# thelast.net
KiCad netlist of a schematic drawn in Altium Designer
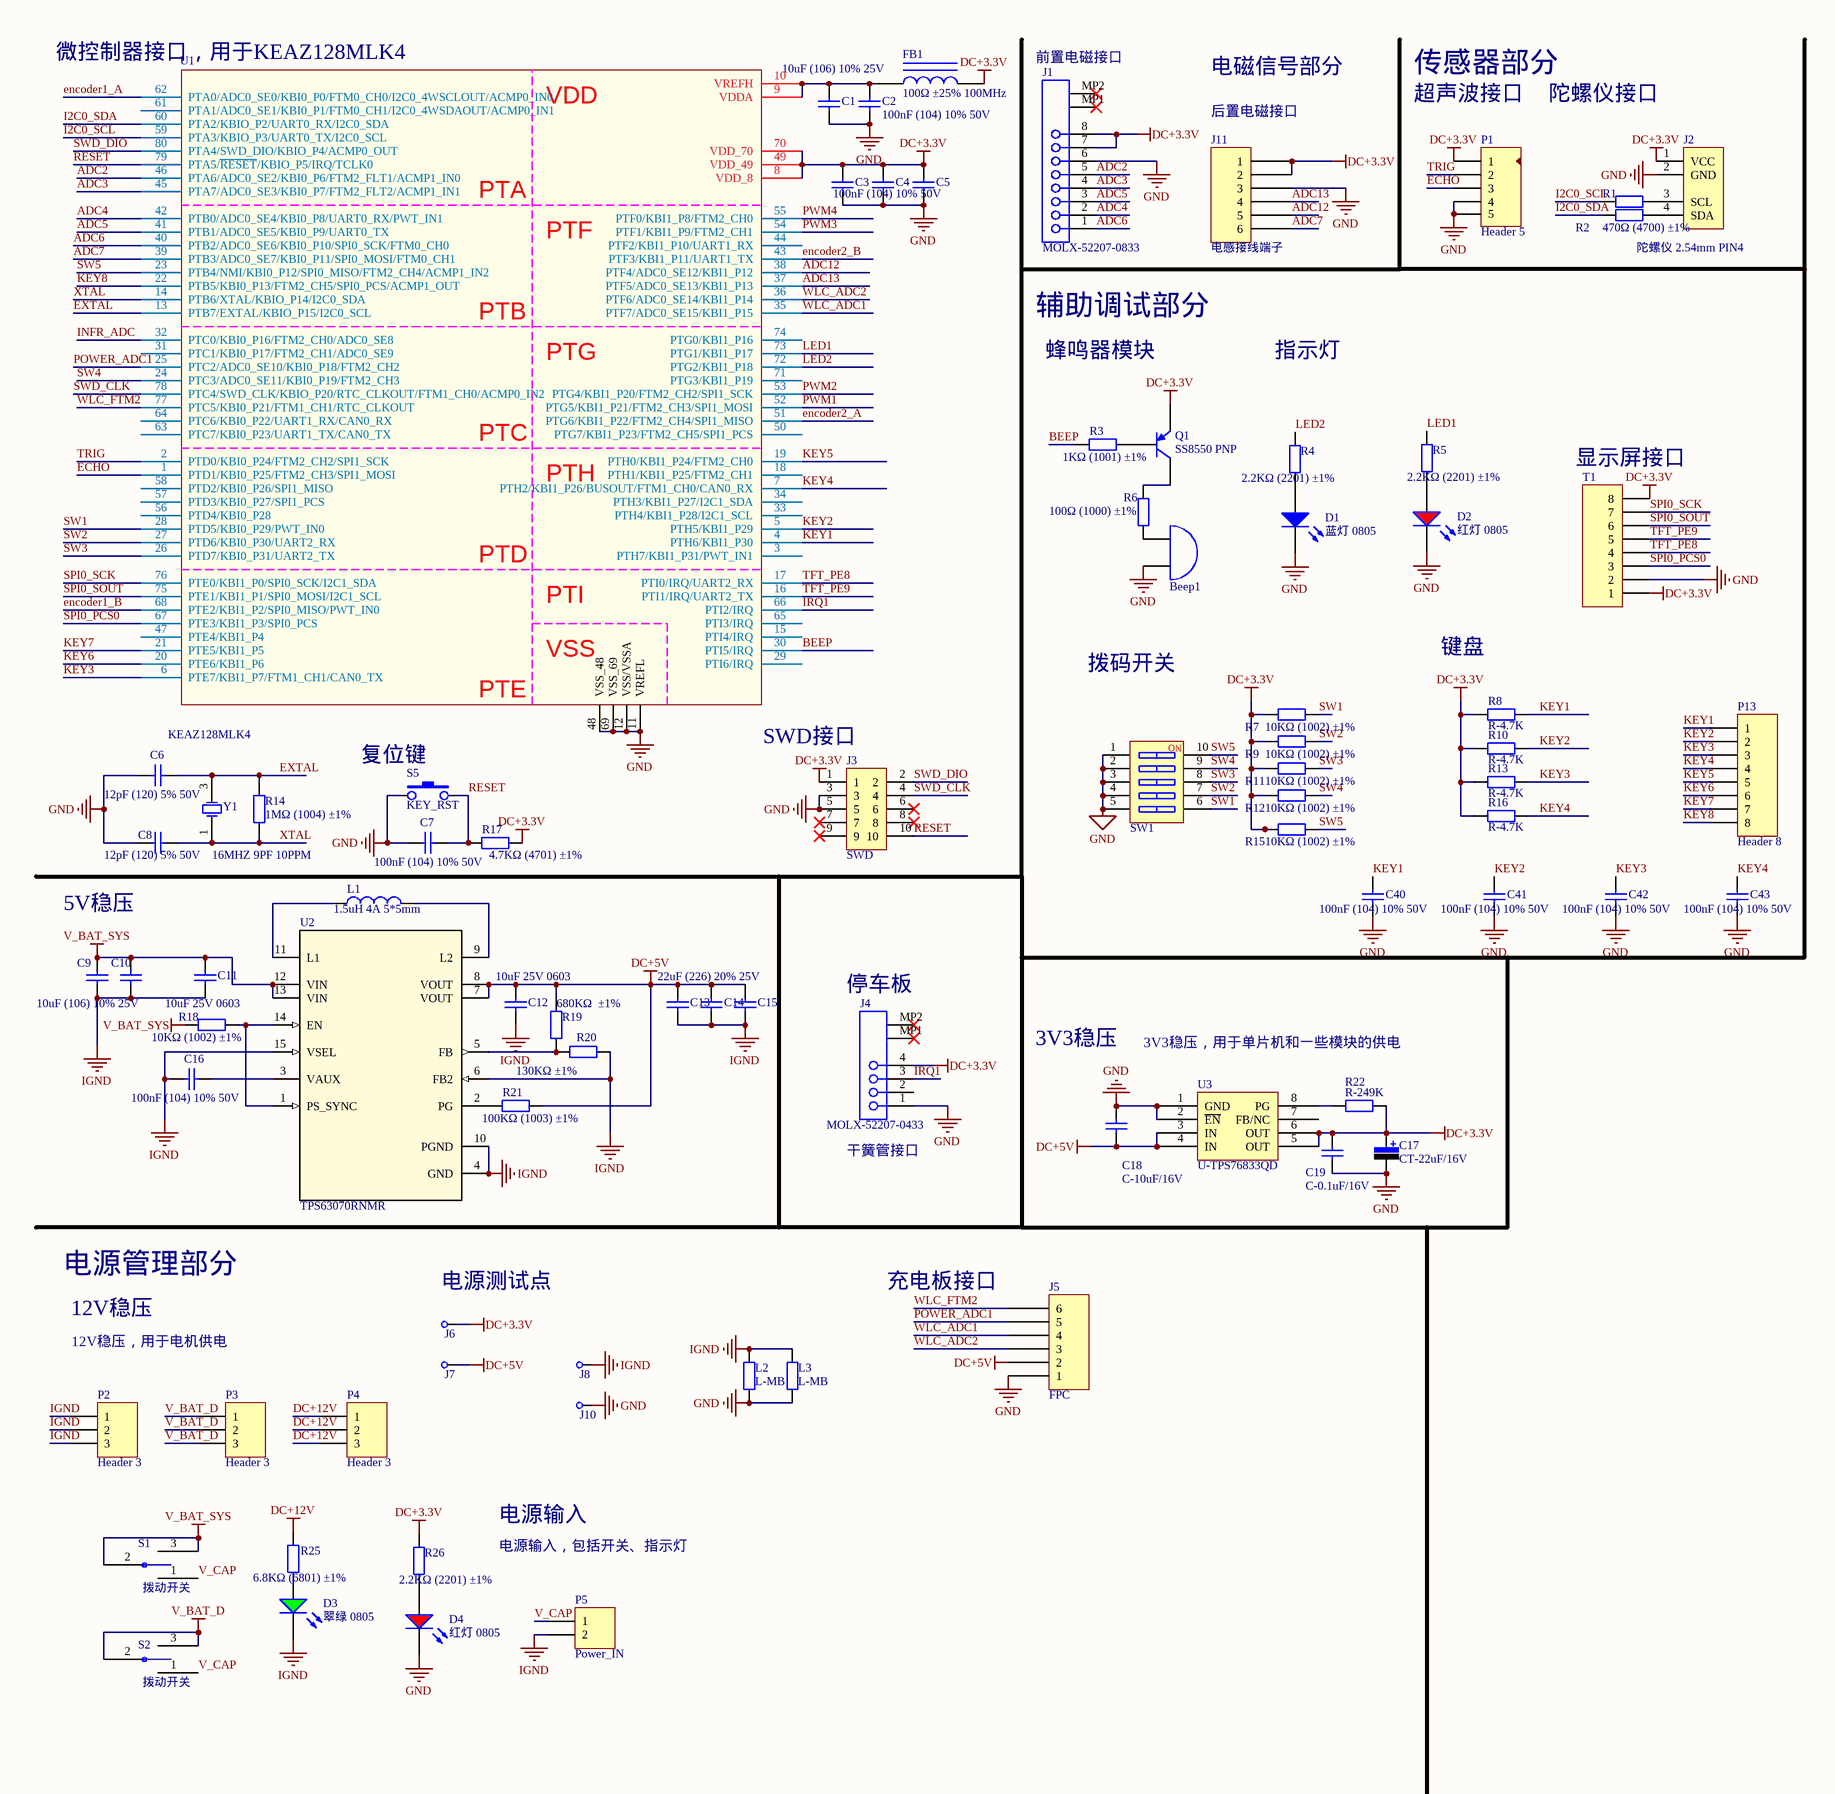
[diagram p0: thelast.SchDoc, left]
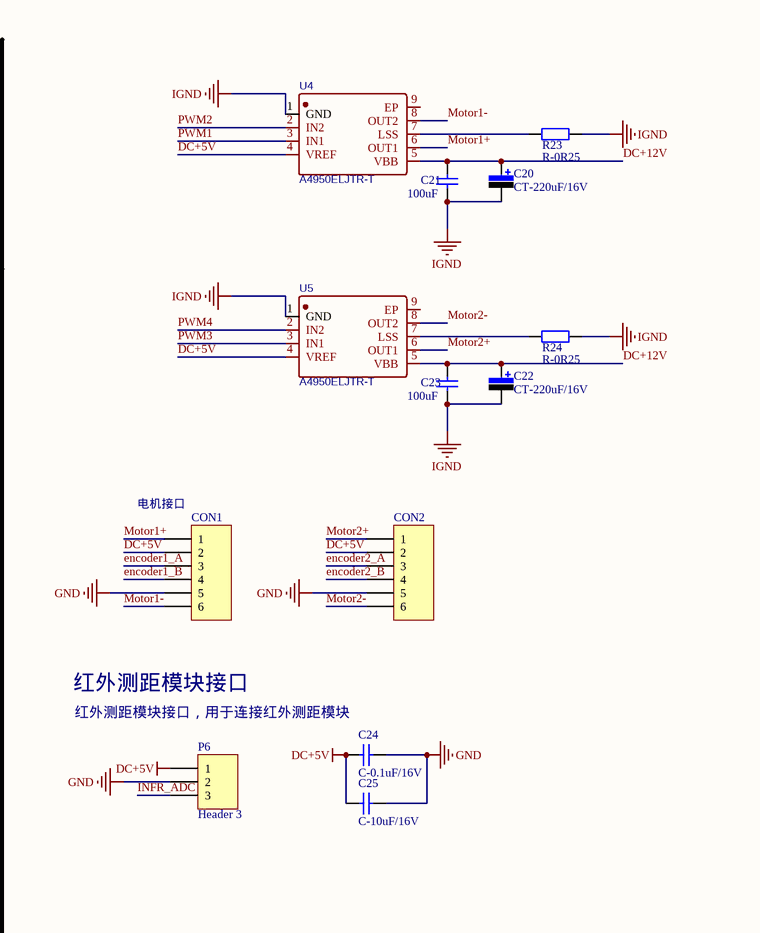
[diagram p1: thelast.SchDoc, right]

(export (version "E")
  (design (tool "Eeschema 10.0.6"))
  (components
    (comp (ref "Beep1") (value "蜂鸣器") (footprint "beep") (libsource (lib "2018NXP") (part "蜂鸣器")))
    (comp (ref "C1")
      (value "10uF (106) 10% 25V")
      (footprint "0603_C")
      (description "贴片电容")
      (libsource (lib "Miscellaneous Devices LC") (part "0805 10uF (106) 10% 25V"))
    )
    (comp (ref "C2")
      (value "100nF (104) 10% 50V")
      (footprint "0603_C")
      (description "贴片电容")
      (libsource (lib "Miscellaneous Devices LC") (part "0603 100nF (104) 10% 50V"))
    )
    (comp (ref "C3")
      (value "100nF (104) 10% 50V")
      (footprint "0603-1")
      (description "贴片电容")
      (libsource (lib "Miscellaneous Devices LC") (part "0603 100nF (104) 10% 50V"))
    )
    (comp (ref "C4")
      (value "100nF (104) 10% 50V")
      (footprint "0603-1")
      (description "贴片电容")
      (libsource (lib "Miscellaneous Devices LC") (part "0603 100nF (104) 10% 50V"))
    )
    (comp (ref "C5")
      (value "100nF (104) 10% 50V")
      (footprint "0603-1")
      (description "贴片电容")
      (libsource (lib "Miscellaneous Devices LC") (part "0603 100nF (104) 10% 50V"))
    )
    (comp (ref "C6")
      (value "12pF (120) 5% 50V")
      (footprint "0603-1")
      (description "贴片电容")
      (libsource (lib "Miscellaneous Devices LC") (part "0603 12pF (120) 5% 50V"))
    )
    (comp (ref "C7")
      (value "100nF (104) 10% 50V")
      (footprint "0603-1")
      (description "贴片电容")
      (libsource (lib "Miscellaneous Devices LC") (part "0603 100nF (104) 10% 50V"))
    )
    (comp (ref "C8")
      (value "12pF (120) 5% 50V")
      (footprint "0603-1")
      (description "贴片电容")
      (libsource (lib "Miscellaneous Devices LC") (part "0603 12pF (120) 5% 50V"))
    )
    (comp (ref "C9")
      (value "10uF (106) 10% 25V")
      (footprint "0805_C")
      (description "贴片电容")
      (libsource (lib "Miscellaneous Devices LC") (part "0805 10uF (106) 10% 25V"))
    )
    (comp (ref "C10")
      (value "10uF (106) 10% 25V")
      (footprint "0805_C")
      (description "贴片电容")
      (libsource (lib "Miscellaneous Devices LC") (part "0805 10uF (106) 10% 25V"))
    )
    (comp (ref "C11")
      (value "10uF 25V 0603")
      (footprint "0603_C")
      (description "贴片电容")
      (libsource (lib "Miscellaneous Devices LC") (part "0603 10uF (106) 10% 10V"))
    )
    (comp (ref "C12")
      (value "10uF 25V 0603")
      (footprint "0603_C")
      (description "贴片电容")
      (libsource (lib "Miscellaneous Devices LC") (part "0603 10uF (106) 10% 10V"))
    )
    (comp (ref "C13")
      (value "22uF (226) 20% 25V")
      (footprint "0805_C")
      (description "贴片电容")
      (libsource (lib "Miscellaneous Devices LC") (part "0805 22uF (226) 20% 25V"))
    )
    (comp (ref "C14")
      (value "22uF (226) 20% 25V")
      (footprint "0805_C")
      (description "贴片电容")
      (libsource (lib "Miscellaneous Devices LC") (part "0805 22uF (226) 20% 25V"))
    )
    (comp (ref "C15")
      (value "22uF (226) 20% 25V")
      (footprint "0805_C")
      (description "贴片电容")
      (libsource (lib "Miscellaneous Devices LC") (part "0805 22uF (226) 20% 25V"))
    )
    (comp (ref "C16")
      (value "100nF (104) 10% 50V")
      (footprint "0603_C")
      (description "贴片电容")
      (libsource (lib "Miscellaneous Devices LC") (part "0603 100nF (104) 10% 50V"))
    )
    (comp (ref "C17")
      (value "CT-22uF/16V")
      (footprint "CAP-3528")
      (description "钽电容")
      (fields (field (name "PUBLISHER") "Altium Limited"))
      (libsource (lib "fszhang") (part "Cap-Pol-A"))
    )
    (comp (ref "C18")
      (value "C-10uF/16V")
      (footprint "0603-1")
      (description "Capacitor")
      (fields (field (name "PUBLISHER") "Altium Limited"))
      (libsource (lib "Miscellaneous Devices") (part "Cap"))
    )
    (comp (ref "C19")
      (value "C-0.1uF/16V")
      (footprint "0603-1")
      (description "Capacitor")
      (fields (field (name "PUBLISHER") "Altium Limited"))
      (libsource (lib "Miscellaneous Devices") (part "Cap"))
    )
    (comp (ref "C20")
      (value "CT-220uF/16V")
      (footprint "CASE-E_7343")
      (description "钽电容")
      (fields (field (name "PUBLISHER") "Altium Limited"))
      (libsource (lib "fszhang") (part "Cap-Pol-A"))
    )
    (comp (ref "C21")
      (value "100uF")
      (footprint "0603-1")
      (description "Capacitor")
      (fields (field (name "PUBLISHER") "Altium Limited"))
      (libsource (lib "Miscellaneous Devices") (part "Cap"))
    )
    (comp (ref "C22")
      (value "CT-220uF/16V")
      (footprint "CASE-E_7343")
      (description "钽电容")
      (fields (field (name "PUBLISHER") "Altium Limited"))
      (libsource (lib "fszhang") (part "Cap-Pol-A"))
    )
    (comp (ref "C23")
      (value "100uF")
      (footprint "0603-1")
      (description "Capacitor")
      (fields (field (name "PUBLISHER") "Altium Limited"))
      (libsource (lib "Miscellaneous Devices") (part "Cap"))
    )
    (comp (ref "C24")
      (value "C-0.1uF/16V")
      (footprint "0603-1")
      (description "Capacitor")
      (fields (field (name "PUBLISHER") "Altium Limited"))
      (libsource (lib "Miscellaneous Devices") (part "Cap"))
    )
    (comp (ref "C25")
      (value "C-10uF/16V")
      (footprint "0603-1")
      (description "Capacitor")
      (fields (field (name "PUBLISHER") "Altium Limited"))
      (libsource (lib "Miscellaneous Devices") (part "Cap"))
    )
    (comp (ref "C40")
      (value "100nF (104) 10% 50V")
      (footprint "0603-1")
      (description "贴片电容")
      (libsource (lib "Miscellaneous Devices LC") (part "0603 100nF (104) 10% 50V"))
    )
    (comp (ref "C41")
      (value "100nF (104) 10% 50V")
      (footprint "0603-1")
      (description "贴片电容")
      (libsource (lib "Miscellaneous Devices LC") (part "0603 100nF (104) 10% 50V"))
    )
    (comp (ref "C42")
      (value "100nF (104) 10% 50V")
      (footprint "0603-1")
      (description "贴片电容")
      (libsource (lib "Miscellaneous Devices LC") (part "0603 100nF (104) 10% 50V"))
    )
    (comp (ref "C43")
      (value "100nF (104) 10% 50V")
      (footprint "0603-1")
      (description "贴片电容")
      (libsource (lib "Miscellaneous Devices LC") (part "0603 100nF (104) 10% 50V"))
    )
    (comp (ref "CON1")
      (value "Header 6")
      (footprint "HDR1X6")
      (description "Header, 6-Pin")
      (fields (field (name "PUBLISHER") "Altium Limited"))
      (libsource (lib "Connectors") (part "Header 6"))
    )
    (comp (ref "CON2")
      (value "Header 6")
      (footprint "HDR1X6")
      (description "Header, 6-Pin")
      (fields (field (name "PUBLISHER") "Altium Limited"))
      (libsource (lib "Connectors") (part "Header 6"))
    )
    (comp (ref "D1")
      (value "蓝灯 0805")
      (footprint "0603_R")
      (description "发光二极管")
      (libsource (lib "Miscellaneous Devices LC") (part "0805 蓝灯"))
    )
    (comp (ref "D2")
      (value "红灯 0805")
      (footprint "0603_R")
      (description "发光二极管")
      (libsource (lib "Miscellaneous Devices LC") (part "0805 红灯"))
    )
    (comp (ref "D3")
      (value "翠绿 0805")
      (footprint "0603_R")
      (description "发光二极管")
      (libsource (lib "Miscellaneous Devices LC") (part "0805 翠绿"))
    )
    (comp (ref "D4")
      (value "红灯 0805")
      (footprint "0603_R")
      (description "发光二极管")
      (libsource (lib "Miscellaneous Devices LC") (part "0805 红灯"))
    )
    (comp (ref "FB1")
      (value "100Ω ±25% 100MHz")
      (footprint "0805-1")
      (description "贴片磁珠")
      (libsource (lib "Miscellaneous Devices LC") (part "0805 100Ω 25% 100MHz"))
    )
    (comp (ref "J1")
      (value "MOLX-52207-0833")
      (footprint "FPC-SMD_8PIN-PITCH1.00-BR_LW10251-08")
      (fields (field (name "MANUFACTURER") "Molex") (field (name "PARTNUMBER") "52207-0833"))
      (libsource (lib "2018NXP") (part "MOLX-52207-0833"))
    )
    (comp (ref "J2")
      (value "陀螺仪 2.54mm PIN4")
      (footprint "2.54排针1X4")
      (libsource (lib "2018NXP") (part "陀螺仪 2.54mm PIN4"))
    )
    (comp (ref "J3") (value "SWD") (footprint "2.54排针2X5") (libsource (lib "2018NXP") (part "SWD PIN-10")))
    (comp (ref "J4")
      (value "MOLX-52207-0433")
      (footprint "MOLX-52207-0433")
      (fields (field (name "MANUFACTURER") "Molex") (field (name "PARTNUMBER") "52207-0433"))
      (libsource (lib "2018NXP") (part "MOLX-52207-0433"))
    )
    (comp (ref "J5") (value "FPC") (footprint "FPC6P") (libsource (lib "") (part "FFC6_1")))
    (comp (ref "J6")
      (value "CHECK")
      (footprint "CHECK-A")
      (description "测试点")
      (libsource (lib "fszhang") (part "CHECK"))
    )
    (comp (ref "J7")
      (value "CHECK")
      (footprint "CHECK-A")
      (description "测试点")
      (libsource (lib "fszhang") (part "CHECK"))
    )
    (comp (ref "J8")
      (value "CHECK")
      (footprint "CHECK-A")
      (description "测试点")
      (libsource (lib "fszhang") (part "CHECK"))
    )
    (comp (ref "J10")
      (value "CHECK")
      (footprint "CHECK-A")
      (description "测试点")
      (libsource (lib "fszhang") (part "CHECK"))
    )
    (comp (ref "J11") (value "电感接线端子") (footprint "FPC6P") (libsource (lib "直立电磁原理图库") (part "FFC6")))
    (comp (ref "L1")
      (value "1.5uH 4A 5*5mm")
      (footprint "Inductor_1.5uH")
      (libsource (lib "2018NXP") (part "贴片电感"))
    )
    (comp (ref "L2")
      (value "L-MB")
      (footprint "0603-1")
      (description "Resistor")
      (fields (field (name "PUBLISHER") "Altium Limited"))
      (libsource (lib "2014-SmartCar-DianCi(V4.0)") (part "Res2"))
    )
    (comp (ref "L3")
      (value "L-MB")
      (footprint "0603-1")
      (description "Resistor")
      (fields (field (name "PUBLISHER") "Altium Limited"))
      (libsource (lib "2014-SmartCar-DianCi(V4.0)") (part "Res2"))
    )
    (comp (ref "P1")
      (value "Header 5")
      (footprint "HDR5X1-2.54")
      (description "接插件")
      (fields (field (name "PUBLISHER") "Altium Limited"))
      (libsource (lib "HDR_fszhang") (part "Header 5"))
    )
    (comp (ref "P2")
      (value "Header 3")
      (footprint "HDR1X3")
      (description "Header, 3-Pin")
      (fields (field (name "PUBLISHER") "Altium Limited"))
      (libsource (lib "Miscellaneous Connectors") (part "Header 3"))
    )
    (comp (ref "P3")
      (value "Header 3")
      (footprint "HDR1X3")
      (description "Header, 3-Pin")
      (fields (field (name "PUBLISHER") "Altium Limited"))
      (libsource (lib "Miscellaneous Connectors") (part "Header 3"))
    )
    (comp (ref "P4")
      (value "Header 3")
      (footprint "HDR1X3")
      (description "Header, 3-Pin")
      (fields (field (name "PUBLISHER") "Altium Limited"))
      (libsource (lib "Miscellaneous Connectors") (part "Header 3"))
    )
    (comp (ref "P5")
      (value "Power_IN")
      (footprint "电源接口")
      (description "Header, 2-Pin")
      (fields (field (name "PUBLISHER") "Altium Limited"))
      (libsource (lib "Miscellaneous Connectors") (part "Header 2"))
    )
    (comp (ref "P6")
      (value "Header 3")
      (footprint "HDR1X3")
      (description "Header, 3-Pin")
      (fields (field (name "PUBLISHER") "Altium Limited"))
      (libsource (lib "Miscellaneous Connectors") (part "Header 3"))
    )
    (comp (ref "P13")
      (value "Header 8")
      (footprint "HDR1X8")
      (description "Header, 8-Pin")
      (fields (field (name "PUBLISHER") "Altium Limited"))
      (libsource (lib "Miscellaneous Connectors") (part "Header 8"))
    )
    (comp (ref "Q1") (value "SS8550 PNP") (footprint "SOT-23Q") (libsource (lib "2018NXP") (part "PNP_1")))
    (comp (ref "R1")
      (value "470Ω (4700) ±1%")
      (footprint "0603_R")
      (description "贴片电阻")
      (libsource (lib "Miscellaneous Devices LC") (part "0603 470Ω (4700) 1%"))
    )
    (comp (ref "R2")
      (value "470Ω (4700) ±1%")
      (footprint "0603_R")
      (description "贴片电阻")
      (libsource (lib "Miscellaneous Devices LC") (part "0603 470Ω (4700) 1%"))
    )
    (comp (ref "R3")
      (value "1KΩ (1001) ±1%")
      (footprint "0603_R")
      (description "贴片电阻")
      (libsource (lib "Miscellaneous Devices LC") (part "0603 1KΩ (1001) 1%"))
    )
    (comp (ref "R4")
      (value "2.2KΩ (2201) ±1%")
      (footprint "0603_R")
      (description "贴片电阻")
      (libsource (lib "Miscellaneous Devices LC") (part "0603 3.3KΩ (3301) 1%"))
    )
    (comp (ref "R5")
      (value "2.2KΩ (2201) ±1%")
      (footprint "0603_R")
      (description "贴片电阻")
      (libsource (lib "Miscellaneous Devices LC") (part "0603 2.2KΩ (2201) 1%"))
    )
    (comp (ref "R6")
      (value "100Ω (1000) ±1%")
      (footprint "0603_R")
      (description "贴片电阻")
      (libsource (lib "Miscellaneous Devices LC") (part "0603 100Ω (1000) 1%"))
    )
    (comp (ref "R7")
      (value "10KΩ (1002) ±1%")
      (footprint "0603_R")
      (description "贴片电阻")
      (libsource (lib "Miscellaneous Devices LC") (part "0603 10KΩ (1002) 1%"))
    )
    (comp (ref "R8")
      (value "R-4.7K")
      (footprint "0603-1")
      (description "Resistor")
      (fields (field (name "PUBLISHER") "Altium Limited"))
      (libsource (lib "Miscellaneous Devices") (part "Res2"))
    )
    (comp (ref "R9")
      (value "10KΩ (1002) ±1%")
      (footprint "0603_R")
      (description "贴片电阻")
      (libsource (lib "Miscellaneous Devices LC") (part "0603 10KΩ (1002) 1%"))
    )
    (comp (ref "R10")
      (value "R-4.7K")
      (footprint "0603-1")
      (description "Resistor")
      (fields (field (name "PUBLISHER") "Altium Limited"))
      (libsource (lib "Miscellaneous Devices") (part "Res2"))
    )
    (comp (ref "R11")
      (value "10KΩ (1002) ±1%")
      (footprint "0603_R")
      (description "贴片电阻")
      (libsource (lib "Miscellaneous Devices LC") (part "0603 10KΩ (1002) 1%"))
    )
    (comp (ref "R12")
      (value "10KΩ (1002) ±1%")
      (footprint "0603_R")
      (description "贴片电阻")
      (libsource (lib "Miscellaneous Devices LC") (part "0603 10KΩ (1002) 1%"))
    )
    (comp (ref "R13")
      (value "R-4.7K")
      (footprint "0603-1")
      (description "Resistor")
      (fields (field (name "PUBLISHER") "Altium Limited"))
      (libsource (lib "Miscellaneous Devices") (part "Res2"))
    )
    (comp (ref "R14")
      (value "1MΩ (1004) ±1%")
      (footprint "0603_R")
      (description "贴片电阻")
      (libsource (lib "Miscellaneous Devices LC") (part "0603 1MΩ (1004) 1%"))
    )
    (comp (ref "R15")
      (value "10KΩ (1002) ±1%")
      (footprint "0603_R")
      (description "贴片电阻")
      (libsource (lib "Miscellaneous Devices LC") (part "0603 10KΩ (1002) 1%"))
    )
    (comp (ref "R16")
      (value "R-4.7K")
      (footprint "0603-1")
      (description "Resistor")
      (fields (field (name "PUBLISHER") "Altium Limited"))
      (libsource (lib "Miscellaneous Devices") (part "Res2"))
    )
    (comp (ref "R17")
      (value "4.7KΩ (4701) ±1%")
      (footprint "0603_R")
      (description "贴片电阻")
      (libsource (lib "Miscellaneous Devices LC") (part "0603 4.7KΩ (4701) 1%"))
    )
    (comp (ref "R18")
      (value "10KΩ (1002) ±1%")
      (footprint "0603_R")
      (description "贴片电阻")
      (libsource (lib "") (part "0603 10KΩ (1002) 1%_1"))
    )
    (comp (ref "R19")
      (value "680KΩ  ±1%")
      (footprint "0603_R")
      (description "贴片电阻")
      (libsource (lib "Miscellaneous Devices LC") (part "0603 330KΩ (3303) 1%"))
    )
    (comp (ref "R20")
      (value "130KΩ ±1%")
      (footprint "0603_R")
      (description "贴片电阻")
      (libsource (lib "Miscellaneous Devices LC") (part "0603 51KΩ (5102) 1%"))
    )
    (comp (ref "R21")
      (value "100KΩ (1003) ±1%")
      (footprint "0603_R")
      (description "贴片电阻")
      (libsource (lib "Miscellaneous Devices LC") (part "0603 100KΩ (1003) 1%"))
    )
    (comp (ref "R22")
      (value "R-249K")
      (footprint "0603-1")
      (description "贴片电阻")
      (fields (field (name "PUBLISHER") "Altium Limited"))
      (libsource (lib "") (part "Res1_1"))
    )
    (comp (ref "R23")
      (value "R-0R25")
      (footprint "2512")
      (description "贴片电阻")
      (fields (field (name "PUBLISHER") "Altium Limited"))
      (libsource (lib "fszhang") (part "Res1"))
    )
    (comp (ref "R24")
      (value "R-0R25")
      (footprint "2512")
      (description "贴片电阻")
      (fields (field (name "PUBLISHER") "Altium Limited"))
      (libsource (lib "fszhang") (part "Res1"))
    )
    (comp (ref "R25")
      (value "6.8KΩ (6801) ±1%")
      (footprint "0603_R")
      (description "贴片电阻")
      (libsource (lib "Miscellaneous Devices LC") (part "0603 3.3KΩ (3301) 1%"))
    )
    (comp (ref "R26")
      (value "2.2KΩ (2201) ±1%")
      (footprint "0603_R")
      (description "贴片电阻")
      (libsource (lib "Miscellaneous Devices LC") (part "0603 2.2KΩ (2201) 1%"))
    )
    (comp (ref "S1") (value "拨动开关") (footprint "SW-TO3") (libsource (lib "2018NXP") (part "拨动开关")))
    (comp (ref "S2") (value "拨动开关") (footprint "SW-TO3") (libsource (lib "2018NXP") (part "拨动开关")))
    (comp (ref "S5")
      (value "KEY_RST")
      (footprint "KEY-K2")
      (description "SMT Tactile ‎Switch")
      (libsource (lib "2018NXP") (part "SMT_SW"))
    )
    (comp (ref "SW1") (value "5P") (footprint "拨码开关DIP-5P") (libsource (lib "2018NXP") (part "拨码开关5P")))
    (comp (ref "T1")
      (value "Header 8")
      (footprint "HDR1X8")
      (description "Header, 8-Pin")
      (fields (field (name "PUBLISHER") "Altium Limited"))
      (libsource (lib "Connectors") (part "Header 8"))
    )
    (comp (ref "U1")
      (value "KEAZ128MLK4")
      (footprint "LQFP80(KEA)")
      (libsource (lib "2018NXP") (part "KEAZ128MLK4"))
    )
    (comp (ref "U2")
      (value "TPS63070RNMR")
      (footprint "RNM0015A")
      (description "Imported")
      (fields (field (name "MANUFACTURER") "Texas Instruments"))
      (libsource (lib "2018NXP") (part "TPS63070RNMR"))
    )
    (comp (ref "U3")
      (value "U-TPS76833QD")
      (footprint "SOIC-8-r")
      (libsource (lib "fszhang") (part "TPS76850"))
    )
    (comp (ref "U4")
      (value "A4950ELJTR-T")
      (footprint "SOIC-8_EP_150MIL")
      (fields (field (name "BOM_SUPPLIER PART") "C82404"))
      (libsource (lib "My_PCB_Lib") (part "A4950ELJTR-T"))
    )
    (comp (ref "U5")
      (value "A4950ELJTR-T")
      (footprint "SOIC-8_EP_150MIL")
      (fields (field (name "BOM_SUPPLIER PART") "C82404"))
      (libsource (lib "My_PCB_Lib") (part "A4950ELJTR-T"))
    )
    (comp (ref "Y1")
      (value "16MHZ 9PF 10PPM")
      (footprint "SMD-3225_4P")
      (description "贴片晶振")
      (libsource (lib "Miscellaneous Devices LC") (part "SMD-3225_4P  16MHZ 9PF 10PPM"))
    )
  )
  (nets
    (net (code "1") (name "/ADC2") (class "Default")
      (node (ref "J1") (pin "5") (pinfunction "5_5") (pintype "passive"))
      (node (ref "U1") (pin "46") (pinfunction "PTA6/ADC0_SE2/KBI0_P6/FTM2_FLT1/ACMP1_IN0_46") (pintype "passive"))
    )
    (net (code "2") (name "/ADC3") (class "Default")
      (node (ref "J1") (pin "4") (pinfunction "4_4") (pintype "passive"))
      (node (ref "U1") (pin "45") (pinfunction "PTA7/ADC0_SE3/KBI0_P7/FTM2_FLT2/ACMP1_IN1_45") (pintype "passive"))
    )
    (net (code "3") (name "/ADC4") (class "Default")
      (node (ref "J1") (pin "2") (pinfunction "2_2") (pintype "passive"))
      (node (ref "U1") (pin "42") (pinfunction "PTB0/ADC0_SE4/KBI0_P8/UART0_RX/PWT_IN1_42") (pintype "passive"))
    )
    (net (code "4") (name "/ADC5") (class "Default")
      (node (ref "J1") (pin "3") (pinfunction "3_3") (pintype "passive"))
      (node (ref "U1") (pin "41") (pinfunction "PTB1/ADC0_SE5/KBI0_P9/UART0_TX_41") (pintype "passive"))
    )
    (net (code "5") (name "/ADC6") (class "Default")
      (node (ref "J1") (pin "1") (pinfunction "1_1") (pintype "passive"))
      (node (ref "U1") (pin "40") (pinfunction "PTB2/ADC0_SE6/KBI0_P10/SPI0_SCK/FTM0_CH0_40") (pintype "passive"))
    )
    (net (code "6") (name "/ADC7") (class "Default")
      (node (ref "J11") (pin "6") (pinfunction "6_6") (pintype "passive"))
      (node (ref "U1") (pin "39") (pinfunction "PTB3/ADC0_SE7/KBI0_P11/SPI0_MOSI/FTM0_CH1_39") (pintype "passive"))
    )
    (net (code "7") (name "/ADC12") (class "Default")
      (node (ref "J11") (pin "5") (pinfunction "5_5") (pintype "passive"))
      (node (ref "U1") (pin "38") (pinfunction "PTF4/ADC0_SE12/KBI1_P12_38") (pintype "passive"))
    )
    (net (code "8") (name "/ADC13") (class "Default")
      (node (ref "J11") (pin "4") (pinfunction "4_4") (pintype "passive"))
      (node (ref "U1") (pin "37") (pinfunction "PTF5/ADC0_SE13/KBI1_P13_37") (pintype "passive"))
    )
    (net (code "9") (name "/BEEP") (class "Default")
      (node (ref "R3") (pin "1") (pinfunction "1_1") (pintype "passive"))
      (node (ref "U1") (pin "30") (pinfunction "PTI5/IRQ_30") (pintype "passive"))
    )
    (net (code "10") (name "/ECHO") (class "Default")
      (node (ref "P1") (pin "3") (pinfunction "3_3") (pintype "passive"))
      (node (ref "U1") (pin "1") (pinfunction "PTD1/KBI0_P25/FTM2_CH3/SPI1_MOSI_1") (pintype "passive"))
    )
    (net (code "11") (name "/EXTAL") (class "Default")
      (node (ref "C6") (pin "2") (pinfunction "2_2") (pintype "passive"))
      (node (ref "R14") (pin "2") (pinfunction "2_2") (pintype "passive"))
      (node (ref "U1") (pin "13") (pinfunction "PTB7/EXTAL/KBIO_P15/I2C0_SCL_13") (pintype "passive"))
      (node (ref "Y1") (pin "3") (pinfunction "OSC2_3") (pintype "passive"))
    )
    (net (code "12") (name "/I2C0_SCL") (class "Default")
      (node (ref "R1") (pin "1") (pinfunction "1_1") (pintype "passive"))
      (node (ref "U1") (pin "59") (pinfunction "PTA3/KBIO_P3/UART0_TX/I2C0_SCL_59") (pintype "passive"))
    )
    (net (code "13") (name "/I2C0_SDA") (class "Default")
      (node (ref "R2") (pin "1") (pinfunction "1_1") (pintype "passive"))
      (node (ref "U1") (pin "60") (pinfunction "PTA2/KBIO_P2/UART0_RX/I2C0_SDA_60") (pintype "passive"))
    )
    (net (code "14") (name "/INFR_ADC") (class "Default")
      (node (ref "P6") (pin "3") (pinfunction "3_3") (pintype "passive"))
      (node (ref "U1") (pin "32") (pinfunction "PTC0/KBI0_P16/FTM2_CH0/ADC0_SE8_32") (pintype "passive"))
    )
    (net (code "15") (name "/IRQ1") (class "Default")
      (node (ref "J4") (pin "3") (pinfunction "3_3") (pintype "passive"))
      (node (ref "U1") (pin "66") (pinfunction "PTI2/IRQ_66") (pintype "passive"))
    )
    (net (code "16") (name "/KEY1") (class "Default")
      (node (ref "C40") (pin "1") (pinfunction "1_1") (pintype "passive"))
      (node (ref "P13") (pin "1") (pinfunction "1_1") (pintype "passive"))
      (node (ref "R8") (pin "2") (pinfunction "2_2") (pintype "passive"))
      (node (ref "U1") (pin "4") (pinfunction "PTH6/KBI1_P30_4") (pintype "passive"))
    )
    (net (code "17") (name "/KEY2") (class "Default")
      (node (ref "C41") (pin "1") (pinfunction "1_1") (pintype "passive"))
      (node (ref "P13") (pin "2") (pinfunction "2_2") (pintype "passive"))
      (node (ref "R10") (pin "2") (pinfunction "2_2") (pintype "passive"))
      (node (ref "U1") (pin "5") (pinfunction "PTH5/KBI1_P29_5") (pintype "passive"))
    )
    (net (code "18") (name "/KEY3") (class "Default")
      (node (ref "C42") (pin "1") (pinfunction "1_1") (pintype "passive"))
      (node (ref "P13") (pin "3") (pinfunction "3_3") (pintype "passive"))
      (node (ref "R13") (pin "2") (pinfunction "2_2") (pintype "passive"))
      (node (ref "U1") (pin "6") (pinfunction "PTE7/KBI1_P7/FTM1_CH1/CAN0_TX_6") (pintype "passive"))
    )
    (net (code "19") (name "/KEY4") (class "Default")
      (node (ref "C43") (pin "1") (pinfunction "1_1") (pintype "passive"))
      (node (ref "P13") (pin "4") (pinfunction "4_4") (pintype "passive"))
      (node (ref "R16") (pin "2") (pinfunction "2_2") (pintype "passive"))
      (node (ref "U1") (pin "7") (pinfunction "PTH2/KBI1_P26/BUSOUT/FTM1_CH0/CAN0_RX_7") (pintype "passive"))
    )
    (net (code "20") (name "/KEY5") (class "Default")
      (node (ref "P13") (pin "5") (pinfunction "5_5") (pintype "passive"))
      (node (ref "U1") (pin "19") (pinfunction "PTH0/KBI1_P24/FTM2_CH0_19") (pintype "passive"))
    )
    (net (code "21") (name "/KEY6") (class "Default")
      (node (ref "P13") (pin "6") (pinfunction "6_6") (pintype "passive"))
      (node (ref "U1") (pin "20") (pinfunction "PTE6/KBI1_P6_20") (pintype "passive"))
    )
    (net (code "22") (name "/KEY7") (class "Default")
      (node (ref "P13") (pin "7") (pinfunction "7_7") (pintype "passive"))
      (node (ref "U1") (pin "21") (pinfunction "PTE5/KBI1_P5_21") (pintype "passive"))
    )
    (net (code "23") (name "/KEY8") (class "Default")
      (node (ref "P13") (pin "8") (pinfunction "8_8") (pintype "passive"))
      (node (ref "U1") (pin "22") (pinfunction "PTB5/KBI0_P13/FTM2_CH5/SPI0_PCS/ACMP1_OUT_22") (pintype "passive"))
    )
    (net (code "24") (name "/LED1") (class "Default")
      (node (ref "R5") (pin "2") (pinfunction "2_2") (pintype "passive"))
      (node (ref "U1") (pin "73") (pinfunction "PTG1/KBI1_P17_73") (pintype "passive"))
    )
    (net (code "25") (name "/LED2") (class "Default")
      (node (ref "R4") (pin "2") (pinfunction "2_2") (pintype "passive"))
      (node (ref "U1") (pin "72") (pinfunction "PTG2/KBI1_P18_72") (pintype "passive"))
    )
    (net (code "26") (name "/Motor1+") (class "Default")
      (node (ref "CON1") (pin "1") (pinfunction "1_1") (pintype "passive"))
      (node (ref "U4") (pin "6") (pinfunction "OUT1_6") (pintype "passive"))
    )
    (net (code "27") (name "/Motor1-") (class "Default")
      (node (ref "CON1") (pin "6") (pinfunction "6_6") (pintype "passive"))
      (node (ref "U4") (pin "8") (pinfunction "OUT2_8") (pintype "passive"))
    )
    (net (code "28") (name "/Motor2+") (class "Default")
      (node (ref "CON2") (pin "1") (pinfunction "1_1") (pintype "passive"))
      (node (ref "U5") (pin "6") (pinfunction "OUT1_6") (pintype "passive"))
    )
    (net (code "29") (name "/Motor2-") (class "Default")
      (node (ref "CON2") (pin "6") (pinfunction "6_6") (pintype "passive"))
      (node (ref "U5") (pin "8") (pinfunction "OUT2_8") (pintype "passive"))
    )
    (net (code "30") (name "/POWER_ADC1") (class "Default")
      (node (ref "J5") (pin "5") (pinfunction "5_5") (pintype "passive"))
      (node (ref "U1") (pin "25") (pinfunction "PTC2/ADC0_SE10/KBI0_P18/FTM2_CH2_25") (pintype "passive"))
    )
    (net (code "31") (name "/PWM1") (class "Default")
      (node (ref "U1") (pin "52") (pinfunction "PTG5/KBI1_P21/FTM2_CH3/SPI1_MOSI_52") (pintype "passive"))
      (node (ref "U4") (pin "3") (pinfunction "IN1_3") (pintype "passive"))
    )
    (net (code "32") (name "/PWM2") (class "Default")
      (node (ref "U1") (pin "53") (pinfunction "PTG4/KBI1_P20/FTM2_CH2/SPI1_SCK_53") (pintype "passive"))
      (node (ref "U4") (pin "2") (pinfunction "IN2_2") (pintype "passive"))
    )
    (net (code "33") (name "/PWM3") (class "Default")
      (node (ref "U1") (pin "54") (pinfunction "PTF1/KBI1_P9/FTM2_CH1_54") (pintype "passive"))
      (node (ref "U5") (pin "3") (pinfunction "IN1_3") (pintype "passive"))
    )
    (net (code "34") (name "/PWM4") (class "Default")
      (node (ref "U1") (pin "55") (pinfunction "PTF0/KBI1_P8/FTM2_CH0_55") (pintype "passive"))
      (node (ref "U5") (pin "2") (pinfunction "IN2_2") (pintype "passive"))
    )
    (net (code "35") (name "/RESET") (class "Default")
      (node (ref "C7") (pin "2") (pinfunction "2_2") (pintype "passive"))
      (node (ref "J3") (pin "10") (pinfunction "10_10") (pintype "passive"))
      (node (ref "R17") (pin "2") (pinfunction "2_2") (pintype "passive"))
      (node (ref "S5") (pin "2") (pinfunction "2_2") (pintype "passive"))
      (node (ref "U1") (pin "79") (pinfunction "PTA5/~{RESET}/KBIO_P5/IRQ/TCLK0_79") (pintype "passive"))
    )
    (net (code "36") (name "/SPI0_PCS0") (class "Default")
      (node (ref "T1") (pin "3") (pinfunction "3_3") (pintype "passive"))
      (node (ref "U1") (pin "67") (pinfunction "PTE3/KBI1_P3/SPI0_PCS_67") (pintype "passive"))
    )
    (net (code "37") (name "/SPI0_SCK") (class "Default")
      (node (ref "T1") (pin "7") (pinfunction "7_7") (pintype "passive"))
      (node (ref "U1") (pin "76") (pinfunction "PTE0/KBI1_P0/SPI0_SCK/I2C1_SDA_76") (pintype "passive"))
    )
    (net (code "38") (name "/SPI0_SOUT") (class "Default")
      (node (ref "T1") (pin "6") (pinfunction "6_6") (pintype "passive"))
      (node (ref "U1") (pin "75") (pinfunction "PTE1/KBI1_P1/SPI0_MOSI/I2C1_SCL_75") (pintype "passive"))
    )
    (net (code "39") (name "/SW1") (class "Default")
      (node (ref "R7") (pin "2") (pinfunction "2_2") (pintype "passive"))
      (node (ref "SW1") (pin "6") (pinfunction "6_6") (pintype "passive"))
      (node (ref "U1") (pin "28") (pinfunction "PTD5/KBI0_P29/PWT_IN0_28") (pintype "passive"))
    )
    (net (code "40") (name "/SW2") (class "Default")
      (node (ref "R9") (pin "2") (pinfunction "2_2") (pintype "passive"))
      (node (ref "SW1") (pin "7") (pinfunction "7_7") (pintype "passive"))
      (node (ref "U1") (pin "27") (pinfunction "PTD6/KBI0_P30/UART2_RX_27") (pintype "passive"))
    )
    (net (code "41") (name "/SW3") (class "Default")
      (node (ref "R11") (pin "2") (pinfunction "2_2") (pintype "passive"))
      (node (ref "SW1") (pin "8") (pinfunction "8_8") (pintype "passive"))
      (node (ref "U1") (pin "26") (pinfunction "PTD7/KBI0_P31/UART2_TX_26") (pintype "passive"))
    )
    (net (code "42") (name "/SW4") (class "Default")
      (node (ref "R12") (pin "2") (pinfunction "2_2") (pintype "passive"))
      (node (ref "SW1") (pin "9") (pinfunction "9_9") (pintype "passive"))
      (node (ref "U1") (pin "24") (pinfunction "PTC3/ADC0_SE11/KBI0_P19/FTM2_CH3_24") (pintype "passive"))
    )
    (net (code "43") (name "/SW5") (class "Default")
      (node (ref "R15") (pin "2") (pinfunction "2_2") (pintype "passive"))
      (node (ref "SW1") (pin "10") (pinfunction "10_10") (pintype "passive"))
      (node (ref "U1") (pin "23") (pinfunction "PTB4/NMI/KBI0_P12/SPI0_MISO/FTM2_CH4/ACMP1_IN2_23") (pintype "passive"))
    )
    (net (code "44") (name "/SWD_CLK") (class "Default")
      (node (ref "J3") (pin "4") (pinfunction "4_4") (pintype "passive"))
      (node (ref "U1") (pin "78") (pinfunction "PTC4/SWD_CLK/KBIO_P20/RTC_CLKOUT/FTM1_CH0/ACMP0_IN2_78") (pintype "passive"))
    )
    (net (code "45") (name "/SWD_DIO") (class "Default")
      (node (ref "J3") (pin "2") (pinfunction "2_2") (pintype "passive"))
      (node (ref "U1") (pin "80") (pinfunction "PTA4/SWD_DIO/KBIO_P4/ACMP0_OUT_80") (pintype "passive"))
    )
    (net (code "46") (name "/TFT_PE8") (class "Default")
      (node (ref "T1") (pin "4") (pinfunction "4_4") (pintype "passive"))
      (node (ref "U1") (pin "17") (pinfunction "PTI0/IRQ/UART2_RX_17") (pintype "passive"))
    )
    (net (code "47") (name "/TFT_PE9") (class "Default")
      (node (ref "T1") (pin "5") (pinfunction "5_5") (pintype "passive"))
      (node (ref "U1") (pin "16") (pinfunction "PTI1/IRQ/UART2_TX_16") (pintype "passive"))
    )
    (net (code "48") (name "/TRIG") (class "Default")
      (node (ref "P1") (pin "2") (pinfunction "2_2") (pintype "passive"))
      (node (ref "U1") (pin "2") (pinfunction "PTD0/KBI0_P24/FTM2_CH2/SPI1_SCK_2") (pintype "passive"))
    )
    (net (code "49") (name "/V_CAP") (class "Default")
      (node (ref "P5") (pin "1") (pinfunction "1_1") (pintype "passive"))
      (node (ref "S1") (pin "1") (pinfunction "1_1") (pintype "passive"))
      (node (ref "S2") (pin "1") (pinfunction "1_1") (pintype "passive"))
    )
    (net (code "50") (name "/WLC_ADC1") (class "Default")
      (node (ref "J5") (pin "4") (pinfunction "4_4") (pintype "passive"))
      (node (ref "U1") (pin "35") (pinfunction "PTF7/ADC0_SE15/KBI1_P15_35") (pintype "passive"))
    )
    (net (code "51") (name "/WLC_ADC2") (class "Default")
      (node (ref "J5") (pin "3") (pinfunction "3_3") (pintype "passive"))
      (node (ref "U1") (pin "36") (pinfunction "PTF6/ADC0_SE14/KBI1_P14_36") (pintype "passive"))
    )
    (net (code "52") (name "/WLC_FTM2") (class "Default")
      (node (ref "J5") (pin "6") (pinfunction "6_6") (pintype "passive"))
      (node (ref "U1") (pin "77") (pinfunction "PTC5/KBI0_P21/FTM1_CH1/RTC_CLKOUT_77") (pintype "passive"))
    )
    (net (code "53") (name "/XTAL") (class "Default")
      (node (ref "C8") (pin "2") (pinfunction "2_2") (pintype "passive"))
      (node (ref "R14") (pin "1") (pinfunction "1_1") (pintype "passive"))
      (node (ref "U1") (pin "14") (pinfunction "PTB6/XTAL/KBIO_P14/I2C0_SDA_14") (pintype "passive"))
      (node (ref "Y1") (pin "1") (pinfunction "OSC1_1") (pintype "passive"))
    )
    (net (code "54") (name "/encoder1_A") (class "Default")
      (node (ref "CON1") (pin "3") (pinfunction "3_3") (pintype "passive"))
      (node (ref "U1") (pin "62") (pinfunction "PTA0/ADC0_SE0/KBI0_P0/FTM0_CH0/I2C0_4WSCLOUT/ACMP0_IN0_62") (pintype "passive"))
    )
    (net (code "55") (name "/encoder1_B") (class "Default")
      (node (ref "CON1") (pin "4") (pinfunction "4_4") (pintype "passive"))
      (node (ref "U1") (pin "68") (pinfunction "PTE2/KBI1_P2/SPI0_MISO/PWT_IN0_68") (pintype "passive"))
    )
    (net (code "56") (name "/encoder2_A") (class "Default")
      (node (ref "CON2") (pin "3") (pinfunction "3_3") (pintype "passive"))
      (node (ref "U1") (pin "51") (pinfunction "PTG6/KBI1_P22/FTM2_CH4/SPI1_MISO_51") (pintype "passive"))
    )
    (net (code "57") (name "/encoder2_B") (class "Default")
      (node (ref "CON2") (pin "4") (pinfunction "4_4") (pintype "passive"))
      (node (ref "U1") (pin "43") (pinfunction "PTF3/KBI1_P11/UART1_TX_43") (pintype "passive"))
    )
    (net (code "58") (name "DC+3.3V") (class "Default")
      (node (ref "C17") (pin "1") (pinfunction "1_1") (pintype "passive"))
      (node (ref "C19") (pin "2") (pinfunction "2_2") (pintype "passive"))
      (node (ref "C3") (pin "2") (pinfunction "2_2") (pintype "passive"))
      (node (ref "C4") (pin "2") (pinfunction "2_2") (pintype "passive"))
      (node (ref "C5") (pin "2") (pinfunction "2_2") (pintype "passive"))
      (node (ref "FB1") (pin "2") (pinfunction "2_2") (pintype "passive"))
      (node (ref "J1") (pin "7") (pinfunction "7_7") (pintype "passive"))
      (node (ref "J1") (pin "8") (pinfunction "8_8") (pintype "passive"))
      (node (ref "J11") (pin "1") (pinfunction "1_1") (pintype "passive"))
      (node (ref "J11") (pin "2") (pinfunction "2_2") (pintype "passive"))
      (node (ref "J2") (pin "1") (pinfunction "VCC_1") (pintype "passive"))
      (node (ref "J3") (pin "1") (pinfunction "1_1") (pintype "passive"))
      (node (ref "J4") (pin "4") (pinfunction "4_4") (pintype "passive"))
      (node (ref "J6") (pin "1") (pinfunction "1_1") (pintype "passive"))
      (node (ref "P1") (pin "1") (pinfunction "1_1") (pintype "passive"))
      (node (ref "Q1") (pin "E") (pinfunction "E_E") (pintype "passive"))
      (node (ref "R10") (pin "1") (pinfunction "1_1") (pintype "passive"))
      (node (ref "R11") (pin "1") (pinfunction "1_1") (pintype "passive"))
      (node (ref "R12") (pin "1") (pinfunction "1_1") (pintype "passive"))
      (node (ref "R13") (pin "1") (pinfunction "1_1") (pintype "passive"))
      (node (ref "R15") (pin "1") (pinfunction "1_1") (pintype "passive"))
      (node (ref "R16") (pin "1") (pinfunction "1_1") (pintype "passive"))
      (node (ref "R17") (pin "1") (pinfunction "1_1") (pintype "passive"))
      (node (ref "R22") (pin "2") (pinfunction "2_2") (pintype "passive"))
      (node (ref "R26") (pin "2") (pinfunction "2_2") (pintype "passive"))
      (node (ref "R7") (pin "1") (pinfunction "1_1") (pintype "passive"))
      (node (ref "R8") (pin "1") (pinfunction "1_1") (pintype "passive"))
      (node (ref "R9") (pin "1") (pinfunction "1_1") (pintype "passive"))
      (node (ref "T1") (pin "1") (pinfunction "1_1") (pintype "passive"))
      (node (ref "T1") (pin "8") (pinfunction "8_8") (pintype "passive"))
      (node (ref "U1") (pin "49") (pinfunction "VDD_49_49") (pintype "passive"))
      (node (ref "U1") (pin "70") (pinfunction "VDD_70_70") (pintype "passive"))
      (node (ref "U1") (pin "8") (pinfunction "VDD_8_8") (pintype "passive"))
      (node (ref "U3") (pin "5") (pinfunction "OUT_5") (pintype "passive"))
      (node (ref "U3") (pin "6") (pinfunction "OUT_6") (pintype "passive"))
    )
    (net (code "59") (name "DC+5V") (class "Default")
      (node (ref "C12") (pin "1") (pinfunction "1_1") (pintype "passive"))
      (node (ref "C13") (pin "2") (pinfunction "2_2") (pintype "passive"))
      (node (ref "C14") (pin "2") (pinfunction "2_2") (pintype "passive"))
      (node (ref "C15") (pin "2") (pinfunction "2_2") (pintype "passive"))
      (node (ref "C18") (pin "1") (pinfunction "1_1") (pintype "passive"))
      (node (ref "C24") (pin "1") (pinfunction "1_1") (pintype "passive"))
      (node (ref "C25") (pin "2") (pinfunction "2_2") (pintype "passive"))
      (node (ref "CON1") (pin "2") (pinfunction "2_2") (pintype "passive"))
      (node (ref "CON2") (pin "2") (pinfunction "2_2") (pintype "passive"))
      (node (ref "J5") (pin "2") (pinfunction "2_2") (pintype "passive"))
      (node (ref "J7") (pin "1") (pinfunction "1_1") (pintype "passive"))
      (node (ref "P6") (pin "1") (pinfunction "1_1") (pintype "passive"))
      (node (ref "R19") (pin "2") (pinfunction "2_2") (pintype "passive"))
      (node (ref "R21") (pin "2") (pinfunction "2_2") (pintype "passive"))
      (node (ref "U2") (pin "7") (pinfunction "VOUT_7") (pintype "power_in"))
      (node (ref "U2") (pin "8") (pinfunction "VOUT_8") (pintype "power_in"))
      (node (ref "U3") (pin "3") (pinfunction "IN_3") (pintype "passive"))
      (node (ref "U3") (pin "4") (pinfunction "IN_4") (pintype "passive"))
      (node (ref "U4") (pin "4") (pinfunction "VREF_4") (pintype "passive"))
      (node (ref "U5") (pin "4") (pinfunction "VREF_4") (pintype "passive"))
    )
    (net (code "60") (name "DC+12V") (class "Default")
      (node (ref "C20") (pin "1") (pinfunction "1_1") (pintype "passive"))
      (node (ref "C21") (pin "2") (pinfunction "2_2") (pintype "passive"))
      (node (ref "C22") (pin "1") (pinfunction "1_1") (pintype "passive"))
      (node (ref "C23") (pin "2") (pinfunction "2_2") (pintype "passive"))
      (node (ref "P4") (pin "1") (pinfunction "1_1") (pintype "passive"))
      (node (ref "P4") (pin "2") (pinfunction "2_2") (pintype "passive"))
      (node (ref "P4") (pin "3") (pinfunction "3_3") (pintype "passive"))
      (node (ref "R25") (pin "2") (pinfunction "2_2") (pintype "passive"))
      (node (ref "U4") (pin "5") (pinfunction "VBB_5") (pintype "passive"))
      (node (ref "U5") (pin "5") (pinfunction "VBB_5") (pintype "passive"))
    )
    (net (code "61") (name "GND") (class "Default")
      (node (ref "Beep1") (pin "2") (pinfunction "B_2") (pintype "passive"))
      (node (ref "C1") (pin "1") (pinfunction "1_1") (pintype "passive"))
      (node (ref "C17") (pin "2") (pinfunction "2_2") (pintype "passive"))
      (node (ref "C18") (pin "2") (pinfunction "2_2") (pintype "passive"))
      (node (ref "C19") (pin "1") (pinfunction "1_1") (pintype "passive"))
      (node (ref "C2") (pin "1") (pinfunction "1_1") (pintype "passive"))
      (node (ref "C24") (pin "2") (pinfunction "2_2") (pintype "passive"))
      (node (ref "C25") (pin "1") (pinfunction "1_1") (pintype "passive"))
      (node (ref "C3") (pin "1") (pinfunction "1_1") (pintype "passive"))
      (node (ref "C4") (pin "1") (pinfunction "1_1") (pintype "passive"))
      (node (ref "C40") (pin "2") (pinfunction "2_2") (pintype "passive"))
      (node (ref "C41") (pin "2") (pinfunction "2_2") (pintype "passive"))
      (node (ref "C42") (pin "2") (pinfunction "2_2") (pintype "passive"))
      (node (ref "C43") (pin "2") (pinfunction "2_2") (pintype "passive"))
      (node (ref "C5") (pin "1") (pinfunction "1_1") (pintype "passive"))
      (node (ref "C6") (pin "1") (pinfunction "1_1") (pintype "passive"))
      (node (ref "C7") (pin "1") (pinfunction "1_1") (pintype "passive"))
      (node (ref "C8") (pin "1") (pinfunction "1_1") (pintype "passive"))
      (node (ref "CON1") (pin "5") (pinfunction "5_5") (pintype "passive"))
      (node (ref "CON2") (pin "5") (pinfunction "5_5") (pintype "passive"))
      (node (ref "D1") (pin "K") (pinfunction "K_K") (pintype "passive"))
      (node (ref "D2") (pin "K") (pinfunction "K_K") (pintype "passive"))
      (node (ref "D4") (pin "K") (pinfunction "K_K") (pintype "passive"))
      (node (ref "J1") (pin "6") (pinfunction "6_6") (pintype "passive"))
      (node (ref "J10") (pin "1") (pinfunction "1_1") (pintype "passive"))
      (node (ref "J11") (pin "3") (pinfunction "3_3") (pintype "passive"))
      (node (ref "J2") (pin "2") (pinfunction "GND_2") (pintype "passive"))
      (node (ref "J3") (pin "3") (pinfunction "3_3") (pintype "passive"))
      (node (ref "J3") (pin "5") (pinfunction "5_5") (pintype "passive"))
      (node (ref "J4") (pin "1") (pinfunction "1_1") (pintype "passive"))
      (node (ref "J5") (pin "1") (pinfunction "1_1") (pintype "passive"))
      (node (ref "L2") (pin "1") (pinfunction "1_1") (pintype "passive"))
      (node (ref "L3") (pin "1") (pinfunction "1_1") (pintype "passive"))
      (node (ref "P1") (pin "4") (pinfunction "4_4") (pintype "passive"))
      (node (ref "P1") (pin "5") (pinfunction "5_5") (pintype "passive"))
      (node (ref "P6") (pin "2") (pinfunction "2_2") (pintype "passive"))
      (node (ref "S5") (pin "1") (pinfunction "1_1") (pintype "passive"))
      (node (ref "SW1") (pin "1") (pinfunction "1_1") (pintype "passive"))
      (node (ref "SW1") (pin "2") (pinfunction "2_2") (pintype "passive"))
      (node (ref "SW1") (pin "3") (pinfunction "3_3") (pintype "passive"))
      (node (ref "SW1") (pin "4") (pinfunction "4_4") (pintype "passive"))
      (node (ref "SW1") (pin "5") (pinfunction "5_5") (pintype "passive"))
      (node (ref "T1") (pin "2") (pinfunction "2_2") (pintype "passive"))
      (node (ref "U1") (pin "11") (pinfunction "VREFL_11") (pintype "passive"))
      (node (ref "U1") (pin "12") (pinfunction "VSS/VSSA_12") (pintype "passive"))
      (node (ref "U1") (pin "48") (pinfunction "VSS_48_48") (pintype "passive"))
      (node (ref "U1") (pin "69") (pinfunction "VSS_69_69") (pintype "passive"))
      (node (ref "U3") (pin "1") (pinfunction "GND_1") (pintype "passive"))
      (node (ref "U3") (pin "2") (pinfunction "~{EN}_2") (pintype "passive"))
    )
    (net (code "62") (name "IGND") (class "Default")
      (node (ref "C10") (pin "1") (pinfunction "1_1") (pintype "passive"))
      (node (ref "C11") (pin "1") (pinfunction "1_1") (pintype "passive"))
      (node (ref "C12") (pin "2") (pinfunction "2_2") (pintype "passive"))
      (node (ref "C13") (pin "1") (pinfunction "1_1") (pintype "passive"))
      (node (ref "C14") (pin "1") (pinfunction "1_1") (pintype "passive"))
      (node (ref "C15") (pin "1") (pinfunction "1_1") (pintype "passive"))
      (node (ref "C16") (pin "1") (pinfunction "1_1") (pintype "passive"))
      (node (ref "C20") (pin "2") (pinfunction "2_2") (pintype "passive"))
      (node (ref "C21") (pin "1") (pinfunction "1_1") (pintype "passive"))
      (node (ref "C22") (pin "2") (pinfunction "2_2") (pintype "passive"))
      (node (ref "C23") (pin "1") (pinfunction "1_1") (pintype "passive"))
      (node (ref "C9") (pin "1") (pinfunction "1_1") (pintype "passive"))
      (node (ref "D3") (pin "K") (pinfunction "K_K") (pintype "passive"))
      (node (ref "J8") (pin "1") (pinfunction "1_1") (pintype "passive"))
      (node (ref "L2") (pin "2") (pinfunction "2_2") (pintype "passive"))
      (node (ref "L3") (pin "2") (pinfunction "2_2") (pintype "passive"))
      (node (ref "P2") (pin "1") (pinfunction "1_1") (pintype "passive"))
      (node (ref "P2") (pin "2") (pinfunction "2_2") (pintype "passive"))
      (node (ref "P2") (pin "3") (pinfunction "3_3") (pintype "passive"))
      (node (ref "P5") (pin "2") (pinfunction "2_2") (pintype "passive"))
      (node (ref "R20") (pin "1") (pinfunction "1_1") (pintype "passive"))
      (node (ref "R23") (pin "1") (pinfunction "1_1") (pintype "passive"))
      (node (ref "R24") (pin "1") (pinfunction "1_1") (pintype "passive"))
      (node (ref "U2") (pin "10") (pinfunction "PGND_10") (pintype "power_in"))
      (node (ref "U2") (pin "15") (pinfunction "VSEL_15") (pintype "input"))
      (node (ref "U2") (pin "4") (pinfunction "GND_4") (pintype "power_in"))
      (node (ref "U2") (pin "6") (pinfunction "FB2_6") (pintype "input"))
      (node (ref "U4") (pin "1") (pinfunction "GND_1") (pintype "passive"))
      (node (ref "U5") (pin "1") (pinfunction "GND_1") (pintype "passive"))
    )
    (net (code "63") (name "Net-(Beep1-A)") (class "Default")
      (node (ref "Beep1") (pin "1") (pinfunction "A_1") (pintype "passive"))
      (node (ref "R6") (pin "1") (pinfunction "1_1") (pintype "passive"))
    )
    (net (code "64") (name "Net-(D1-PadA)") (class "Default")
      (node (ref "D1") (pin "A") (pinfunction "A_A") (pintype "passive"))
      (node (ref "R4") (pin "1") (pinfunction "1_1") (pintype "passive"))
    )
    (net (code "65") (name "Net-(D2-PadA)") (class "Default")
      (node (ref "D2") (pin "A") (pinfunction "A_A") (pintype "passive"))
      (node (ref "R5") (pin "1") (pinfunction "1_1") (pintype "passive"))
    )
    (net (code "66") (name "Net-(D3-PadA)") (class "Default")
      (node (ref "D3") (pin "A") (pinfunction "A_A") (pintype "passive"))
      (node (ref "R25") (pin "1") (pinfunction "1_1") (pintype "passive"))
    )
    (net (code "67") (name "Net-(D4-PadA)") (class "Default")
      (node (ref "D4") (pin "A") (pinfunction "A_A") (pintype "passive"))
      (node (ref "R26") (pin "1") (pinfunction "1_1") (pintype "passive"))
    )
    (net (code "68") (name "Net-(J2-SCL)") (class "Default")
      (node (ref "J2") (pin "3") (pinfunction "SCL_3") (pintype "passive"))
      (node (ref "R1") (pin "2") (pinfunction "2_2") (pintype "passive"))
    )
    (net (code "69") (name "Net-(J2-SDA)") (class "Default")
      (node (ref "J2") (pin "4") (pinfunction "SDA_4") (pintype "passive"))
      (node (ref "R2") (pin "2") (pinfunction "2_2") (pintype "passive"))
    )
    (net (code "70") (name "Net-(Q1-PadB)") (class "Default")
      (node (ref "Q1") (pin "B") (pinfunction "B_B") (pintype "passive"))
      (node (ref "R3") (pin "2") (pinfunction "2_2") (pintype "passive"))
    )
    (net (code "71") (name "Net-(Q1-PadC)") (class "Default")
      (node (ref "Q1") (pin "C") (pinfunction "C_C") (pintype "passive"))
      (node (ref "R6") (pin "2") (pinfunction "2_2") (pintype "passive"))
    )
    (net (code "72") (name "Net-(U1-VDDA)") (class "Default")
      (node (ref "C1") (pin "2") (pinfunction "2_2") (pintype "passive"))
      (node (ref "C2") (pin "2") (pinfunction "2_2") (pintype "passive"))
      (node (ref "FB1") (pin "1") (pinfunction "1_1") (pintype "passive"))
      (node (ref "U1") (pin "10") (pinfunction "VREFH_10") (pintype "passive"))
      (node (ref "U1") (pin "9") (pinfunction "VDDA_9") (pintype "passive"))
    )
    (net (code "73") (name "Net-(U2-EN)") (class "Default")
      (node (ref "R18") (pin "1") (pinfunction "1_1") (pintype "passive"))
      (node (ref "U2") (pin "1") (pinfunction "PS_SYNC_1") (pintype "input"))
      (node (ref "U2") (pin "14") (pinfunction "EN_14") (pintype "input"))
    )
    (net (code "74") (name "Net-(U2-FB)") (class "Default")
      (node (ref "R19") (pin "1") (pinfunction "1_1") (pintype "passive"))
      (node (ref "R20") (pin "2") (pinfunction "2_2") (pintype "passive"))
      (node (ref "U2") (pin "5") (pinfunction "FB_5") (pintype "output"))
    )
    (net (code "75") (name "Net-(U2-L1)") (class "Default")
      (node (ref "L1") (pin "1") (pinfunction "1_1") (pintype "passive"))
      (node (ref "U2") (pin "11") (pinfunction "L1_11") (pintype "passive"))
    )
    (net (code "76") (name "Net-(U2-L2)") (class "Default")
      (node (ref "L1") (pin "2") (pinfunction "2_2") (pintype "passive"))
      (node (ref "U2") (pin "9") (pinfunction "L2_9") (pintype "passive"))
    )
    (net (code "77") (name "Net-(U2-PG)") (class "Default")
      (node (ref "R21") (pin "1") (pinfunction "1_1") (pintype "passive"))
      (node (ref "U2") (pin "2") (pinfunction "PG_2") (pintype "open_collector"))
    )
    (net (code "78") (name "Net-(U2-VAUX)") (class "Default")
      (node (ref "C16") (pin "2") (pinfunction "2_2") (pintype "passive"))
      (node (ref "U2") (pin "3") (pinfunction "VAUX_3") (pintype "passive"))
    )
    (net (code "79") (name "Net-(U3-PG)") (class "Default")
      (node (ref "R22") (pin "1") (pinfunction "1_1") (pintype "passive"))
      (node (ref "U3") (pin "8") (pinfunction "PG_8") (pintype "passive"))
    )
    (net (code "80") (name "Net-(U4-LSS)") (class "Default")
      (node (ref "R23") (pin "2") (pinfunction "2_2") (pintype "passive"))
      (node (ref "U4") (pin "7") (pinfunction "LSS_7") (pintype "passive"))
    )
    (net (code "81") (name "Net-(U5-LSS)") (class "Default")
      (node (ref "R24") (pin "2") (pinfunction "2_2") (pintype "passive"))
      (node (ref "U5") (pin "7") (pinfunction "LSS_7") (pintype "passive"))
    )
    (net (code "82") (name "V_BAT_D") (class "Default")
      (node (ref "P3") (pin "1") (pinfunction "1_1") (pintype "passive"))
      (node (ref "P3") (pin "2") (pinfunction "2_2") (pintype "passive"))
      (node (ref "P3") (pin "3") (pinfunction "3_3") (pintype "passive"))
      (node (ref "S2") (pin "2") (pinfunction "2_2") (pintype "passive"))
      (node (ref "S2") (pin "3") (pinfunction "3_3") (pintype "passive"))
    )
    (net (code "83") (name "V_BAT_SYS") (class "Default")
      (node (ref "C10") (pin "2") (pinfunction "2_2") (pintype "passive"))
      (node (ref "C11") (pin "2") (pinfunction "2_2") (pintype "passive"))
      (node (ref "C9") (pin "2") (pinfunction "2_2") (pintype "passive"))
      (node (ref "R18") (pin "2") (pinfunction "2_2") (pintype "passive"))
      (node (ref "S1") (pin "2") (pinfunction "2_2") (pintype "passive"))
      (node (ref "S1") (pin "3") (pinfunction "3_3") (pintype "passive"))
      (node (ref "U2") (pin "12") (pinfunction "VIN_12") (pintype "power_in"))
      (node (ref "U2") (pin "13") (pinfunction "VIN_13") (pintype "power_in"))
    )
    (net (code "84") (name "unconnected-(J1-PadMP1)") (class "Default")
      (node (ref "J1") (pin "MP1") (pinfunction "MP1_MP1") (pintype "passive+no_connect"))
    )
    (net (code "85") (name "unconnected-(J1-PadMP2)") (class "Default")
      (node (ref "J1") (pin "MP2") (pinfunction "MP2_MP2") (pintype "passive+no_connect"))
    )
    (net (code "86") (name "unconnected-(J3-Pad6)") (class "Default")
      (node (ref "J3") (pin "6") (pinfunction "6_6") (pintype "passive+no_connect"))
    )
    (net (code "87") (name "unconnected-(J3-Pad7)") (class "Default")
      (node (ref "J3") (pin "7") (pinfunction "7_7") (pintype "passive+no_connect"))
    )
    (net (code "88") (name "unconnected-(J3-Pad8)") (class "Default")
      (node (ref "J3") (pin "8") (pinfunction "8_8") (pintype "passive+no_connect"))
    )
    (net (code "89") (name "unconnected-(J3-Pad9)") (class "Default")
      (node (ref "J3") (pin "9") (pinfunction "9_9") (pintype "passive+no_connect"))
    )
    (net (code "90") (name "unconnected-(J4-Pad2)") (class "Default")
      (node (ref "J4") (pin "2") (pinfunction "2_2") (pintype "passive"))
    )
    (net (code "91") (name "unconnected-(J4-PadMP1)") (class "Default")
      (node (ref "J4") (pin "MP1") (pinfunction "MP1_MP1") (pintype "passive+no_connect"))
    )
    (net (code "92") (name "unconnected-(J4-PadMP2)") (class "Default")
      (node (ref "J4") (pin "MP2") (pinfunction "MP2_MP2") (pintype "passive+no_connect"))
    )
    (net (code "93") (name "unconnected-(U1-PTA1{slash}ADC0_SE1{slash}KBI0_P1{slash}FTM0_CH1{slash}I2C0_4WSDAOUT{slash}ACMP0_IN1-Pad61)") (class "Default")
      (node (ref "U1") (pin "61") (pinfunction "PTA1/ADC0_SE1/KBI0_P1/FTM0_CH1/I2C0_4WSDAOUT/ACMP0_IN1_61") (pintype "passive"))
    )
    (net (code "94") (name "unconnected-(U1-PTC1{slash}KBI0_P17{slash}FTM2_CH1{slash}ADC0_SE9-Pad31)") (class "Default")
      (node (ref "U1") (pin "31") (pinfunction "PTC1/KBI0_P17/FTM2_CH1/ADC0_SE9_31") (pintype "passive"))
    )
    (net (code "95") (name "unconnected-(U1-PTC6{slash}KBI0_P22{slash}UART1_RX{slash}CAN0_RX-Pad64)") (class "Default")
      (node (ref "U1") (pin "64") (pinfunction "PTC6/KBI0_P22/UART1_RX/CAN0_RX_64") (pintype "passive"))
    )
    (net (code "96") (name "unconnected-(U1-PTC7{slash}KBI0_P23{slash}UART1_TX{slash}CAN0_TX-Pad63)") (class "Default")
      (node (ref "U1") (pin "63") (pinfunction "PTC7/KBI0_P23/UART1_TX/CAN0_TX_63") (pintype "passive"))
    )
    (net (code "97") (name "unconnected-(U1-PTD2{slash}KBI0_P26{slash}SPI1_MISO-Pad58)") (class "Default")
      (node (ref "U1") (pin "58") (pinfunction "PTD2/KBI0_P26/SPI1_MISO_58") (pintype "passive"))
    )
    (net (code "98") (name "unconnected-(U1-PTD3{slash}KBI0_P27{slash}SPI1_PCS-Pad57)") (class "Default")
      (node (ref "U1") (pin "57") (pinfunction "PTD3/KBI0_P27/SPI1_PCS_57") (pintype "passive"))
    )
    (net (code "99") (name "unconnected-(U1-PTD4{slash}KBI0_P28-Pad56)") (class "Default")
      (node (ref "U1") (pin "56") (pinfunction "PTD4/KBI0_P28_56") (pintype "passive"))
    )
    (net (code "100") (name "unconnected-(U1-PTE4{slash}KBI1_P4-Pad47)") (class "Default")
      (node (ref "U1") (pin "47") (pinfunction "PTE4/KBI1_P4_47") (pintype "passive"))
    )
    (net (code "101") (name "unconnected-(U1-PTF2{slash}KBI1_P10{slash}UART1_RX-Pad44)") (class "Default")
      (node (ref "U1") (pin "44") (pinfunction "PTF2/KBI1_P10/UART1_RX_44") (pintype "passive"))
    )
    (net (code "102") (name "unconnected-(U1-PTG0{slash}KBI1_P16-Pad74)") (class "Default")
      (node (ref "U1") (pin "74") (pinfunction "PTG0/KBI1_P16_74") (pintype "passive"))
    )
    (net (code "103") (name "unconnected-(U1-PTG3{slash}KBI1_P19-Pad71)") (class "Default")
      (node (ref "U1") (pin "71") (pinfunction "PTG3/KBI1_P19_71") (pintype "passive"))
    )
    (net (code "104") (name "unconnected-(U1-PTG7{slash}KBI1_P23{slash}FTM2_CH5{slash}SPI1_PCS-Pad50)") (class "Default")
      (node (ref "U1") (pin "50") (pinfunction "PTG7/KBI1_P23/FTM2_CH5/SPI1_PCS_50") (pintype "passive"))
    )
    (net (code "105") (name "unconnected-(U1-PTH1{slash}KBI1_P25{slash}FTM2_CH1-Pad18)") (class "Default")
      (node (ref "U1") (pin "18") (pinfunction "PTH1/KBI1_P25/FTM2_CH1_18") (pintype "passive"))
    )
    (net (code "106") (name "unconnected-(U1-PTH3{slash}KBI1_P27{slash}I2C1_SDA-Pad34)") (class "Default")
      (node (ref "U1") (pin "34") (pinfunction "PTH3/KBI1_P27/I2C1_SDA_34") (pintype "passive"))
    )
    (net (code "107") (name "unconnected-(U1-PTH4{slash}KBI1_P28{slash}I2C1_SCL-Pad33)") (class "Default")
      (node (ref "U1") (pin "33") (pinfunction "PTH4/KBI1_P28/I2C1_SCL_33") (pintype "passive"))
    )
    (net (code "108") (name "unconnected-(U1-PTH7{slash}KBI1_P31{slash}PWT_IN1-Pad3)") (class "Default")
      (node (ref "U1") (pin "3") (pinfunction "PTH7/KBI1_P31/PWT_IN1_3") (pintype "passive"))
    )
    (net (code "109") (name "unconnected-(U1-PTI3{slash}IRQ-Pad65)") (class "Default")
      (node (ref "U1") (pin "65") (pinfunction "PTI3/IRQ_65") (pintype "passive"))
    )
    (net (code "110") (name "unconnected-(U1-PTI4{slash}IRQ-Pad15)") (class "Default")
      (node (ref "U1") (pin "15") (pinfunction "PTI4/IRQ_15") (pintype "passive"))
    )
    (net (code "111") (name "unconnected-(U1-PTI6{slash}IRQ-Pad29)") (class "Default")
      (node (ref "U1") (pin "29") (pinfunction "PTI6/IRQ_29") (pintype "passive"))
    )
    (net (code "112") (name "unconnected-(U3-FB{slash}NC-Pad7)") (class "Default")
      (node (ref "U3") (pin "7") (pinfunction "FB/NC_7") (pintype "passive"))
    )
    (net (code "113") (name "unconnected-(U4-EP-Pad9)") (class "Default")
      (node (ref "U4") (pin "9") (pinfunction "EP_9") (pintype "passive"))
    )
    (net (code "114") (name "unconnected-(U5-EP-Pad9)") (class "Default")
      (node (ref "U5") (pin "9") (pinfunction "EP_9") (pintype "passive"))
    )
  )
)
